# Reaccion-vReg.net
KiCad netlist of a schematic drawn in EAGLE
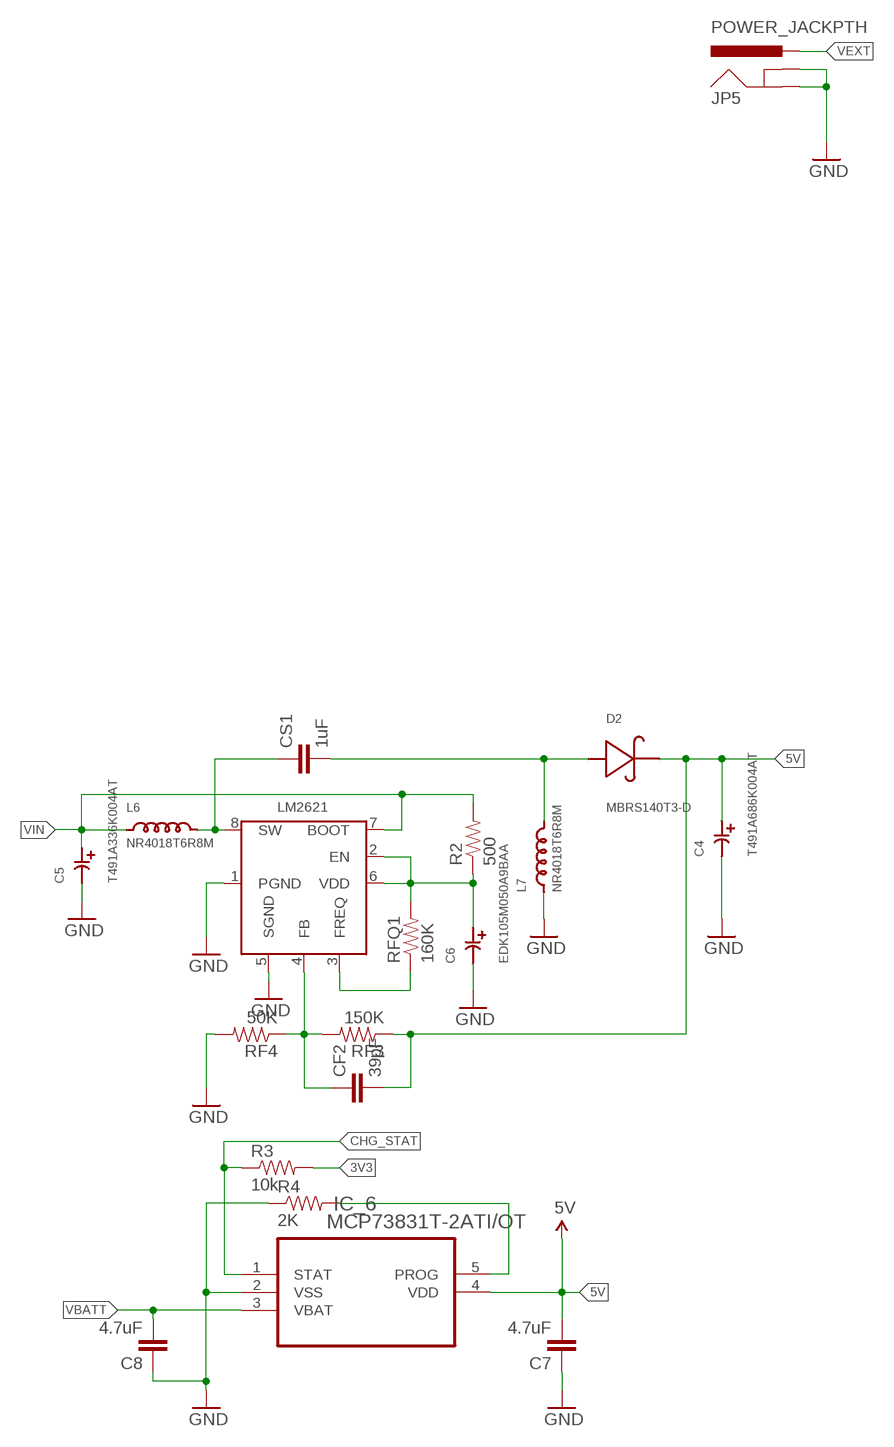
[diagram p0: schematic, sheet 1]

(export (version "E")
  (design (tool "Eeschema 10.0.6"))
  (components
    (comp (ref "C4")
      (value "T491A686K004AT")
      (footprint "eagle-import:3216-18")
      (libsource (lib "eagle-import") (part "T491A686K004AT"))
    )
    (comp (ref "C5")
      (value "T491A336K004AT")
      (footprint "eagle-import:3216-18")
      (libsource (lib "eagle-import") (part "T491A336K004AT"))
    )
    (comp (ref "C6")
      (value "EDK105M050A9BAA")
      (footprint "eagle-import:EDK105M050A9BAA")
      (libsource (lib "eagle-import") (part "EDK105M050A9BAA"))
    )
    (comp (ref "C7")
      (value "4.7uF")
      (footprint "eagle-import:0805")
      (libsource (lib "eagle-import") (part "CAP0805"))
    )
    (comp (ref "C8")
      (value "4.7uF")
      (footprint "eagle-import:0805")
      (libsource (lib "eagle-import") (part "CAP0805"))
    )
    (comp (ref "CF2")
      (value "39pF")
      (footprint "eagle-import:0805")
      (libsource (lib "eagle-import") (part "CAP0805"))
    )
    (comp (ref "CS1")
      (value "1uF")
      (footprint "eagle-import:0805")
      (libsource (lib "eagle-import") (part "CAP0805"))
    )
    (comp (ref "D2")
      (value "MBRS140T3-D")
      (footprint "eagle-import:MBRS140T3G")
      (libsource (lib "eagle-import") (part "MBRS140T3-D"))
    )
    (comp (ref "IC_4")
      (value "LM2621")
      (footprint "eagle-import:R-PDSO-G8")
      (libsource (lib "eagle-import") (part "LM2621"))
    )
    (comp (ref "IC_6")
      (value "MCP73831T-2ATI/OT")
      (footprint "eagle-import:SOT95P300X145-5N")
      (libsource (lib "eagle-import") (part "MCP73831T-2ATI/OT"))
    )
    (comp (ref "JP5")
      (value "POWER_JACKPTH")
      (footprint "eagle-import:POWER_JACK_PTH")
      (libsource (lib "eagle-import") (part "POWER_JACKPTH"))
    )
    (comp (ref "L6")
      (value "NR4018T6R8M")
      (footprint "eagle-import:NR4018_NRS4018")
      (libsource (lib "eagle-import") (part "NR4018T6R8M"))
    )
    (comp (ref "L7")
      (value "NR4018T6R8M")
      (footprint "eagle-import:NR4018_NRS4018")
      (libsource (lib "eagle-import") (part "NR4018T6R8M"))
    )
    (comp (ref "R2")
      (value "500")
      (footprint "eagle-import:0805")
      (libsource (lib "eagle-import") (part "RESISTOR0805-RES"))
    )
    (comp (ref "R3")
      (value "10k")
      (footprint "eagle-import:0805")
      (libsource (lib "eagle-import") (part "RESISTOR0805-RES"))
    )
    (comp (ref "R4")
      (value "2K")
      (footprint "eagle-import:0805")
      (libsource (lib "eagle-import") (part "RESISTOR0805-RES"))
    )
    (comp (ref "RF3")
      (value "150K")
      (footprint "eagle-import:0805")
      (libsource (lib "eagle-import") (part "RESISTOR0805-RES"))
    )
    (comp (ref "RF4")
      (value "50K")
      (footprint "eagle-import:0805")
      (libsource (lib "eagle-import") (part "RESISTOR0805-RES"))
    )
    (comp (ref "RFQ1")
      (value "160K")
      (footprint "eagle-import:0805")
      (libsource (lib "eagle-import") (part "RESISTOR0805-RES"))
    )
  )
  (nets
    (net (code "1") (name "3V3") (class "Default")
      (node (ref "R3") (pin "2") (pinfunction "2_2") (pintype "passive"))
    )
    (net (code "2") (name "5V") (class "Default")
      (node (ref "C4") (pin "1") (pinfunction "P$1_1") (pintype "bidirectional"))
      (node (ref "C7") (pin "2") (pinfunction "2_2") (pintype "passive"))
      (node (ref "CF2") (pin "2") (pinfunction "2_2") (pintype "passive"))
      (node (ref "D2") (pin "2") (pinfunction "2_2") (pintype "bidirectional"))
      (node (ref "IC_6") (pin "4") (pinfunction "VDD_4") (pintype "power_in"))
      (node (ref "RF3") (pin "1") (pinfunction "1_1") (pintype "passive"))
    )
    (net (code "3") (name "CHG_STAT") (class "Default")
      (node (ref "IC_6") (pin "1") (pinfunction "STAT_1") (pintype "input"))
      (node (ref "R3") (pin "1") (pinfunction "1_1") (pintype "passive"))
    )
    (net (code "4") (name "GND") (class "Default")
      (node (ref "C4") (pin "2") (pinfunction "P$2_2") (pintype "bidirectional"))
      (node (ref "C5") (pin "2") (pinfunction "P$2_2") (pintype "bidirectional"))
      (node (ref "C6") (pin "P$2") (pinfunction "P$2_P$2") (pintype "bidirectional"))
      (node (ref "C7") (pin "1") (pinfunction "1_1") (pintype "passive"))
      (node (ref "C8") (pin "1") (pinfunction "1_1") (pintype "passive"))
      (node (ref "IC_4") (pin "1") (pinfunction "PGND_1") (pintype "bidirectional"))
      (node (ref "IC_4") (pin "5") (pinfunction "SGND_5") (pintype "bidirectional"))
      (node (ref "IC_6") (pin "2") (pinfunction "VSS_2") (pintype "passive"))
      (node (ref "JP5") (pin "GND") (pinfunction "GND_GND") (pintype "bidirectional"))
      (node (ref "JP5") (pin "GNDBREAK") (pinfunction "GNDBREAK_GNDBREAK") (pintype "bidirectional"))
      (node (ref "L7") (pin "P$1") (pinfunction "P$1_P$1") (pintype "bidirectional"))
      (node (ref "R4") (pin "1") (pinfunction "1_1") (pintype "passive"))
      (node (ref "RF4") (pin "2") (pinfunction "2_2") (pintype "passive"))
    )
    (net (code "5") (name "Net-(CS1-Pad2)") (class "Default")
      (node (ref "CS1") (pin "2") (pinfunction "2_2") (pintype "passive"))
      (node (ref "D2") (pin "1") (pinfunction "1_1") (pintype "bidirectional"))
      (node (ref "L7") (pin "P$2") (pinfunction "P$2_P$2") (pintype "bidirectional"))
    )
    (net (code "6") (name "Net-(IC_4-EN)") (class "Default")
      (node (ref "C6") (pin "P$1") (pinfunction "P$1_P$1") (pintype "bidirectional"))
      (node (ref "IC_4") (pin "2") (pinfunction "EN_2") (pintype "bidirectional"))
      (node (ref "IC_4") (pin "6") (pinfunction "VDD_6") (pintype "bidirectional"))
      (node (ref "R2") (pin "1") (pinfunction "1_1") (pintype "passive"))
      (node (ref "RFQ1") (pin "2") (pinfunction "2_2") (pintype "passive"))
    )
    (net (code "7") (name "Net-(IC_4-FB)") (class "Default")
      (node (ref "CF2") (pin "1") (pinfunction "1_1") (pintype "passive"))
      (node (ref "IC_4") (pin "4") (pinfunction "FB_4") (pintype "bidirectional"))
      (node (ref "RF3") (pin "2") (pinfunction "2_2") (pintype "passive"))
      (node (ref "RF4") (pin "1") (pinfunction "1_1") (pintype "passive"))
    )
    (net (code "8") (name "Net-(IC_4-FREQ)") (class "Default")
      (node (ref "IC_4") (pin "3") (pinfunction "FREQ_3") (pintype "bidirectional"))
      (node (ref "RFQ1") (pin "1") (pinfunction "1_1") (pintype "passive"))
    )
    (net (code "9") (name "Net-(IC_4-SW)") (class "Default")
      (node (ref "CS1") (pin "1") (pinfunction "1_1") (pintype "passive"))
      (node (ref "IC_4") (pin "8") (pinfunction "SW_8") (pintype "bidirectional"))
      (node (ref "L6") (pin "P$2") (pinfunction "P$2_P$2") (pintype "bidirectional"))
    )
    (net (code "10") (name "Net-(IC_6-PROG)") (class "Default")
      (node (ref "IC_6") (pin "5") (pinfunction "PROG_5") (pintype "input"))
      (node (ref "R4") (pin "2") (pinfunction "2_2") (pintype "passive"))
    )
    (net (code "11") (name "VBATT") (class "Default")
      (node (ref "C8") (pin "2") (pinfunction "2_2") (pintype "passive"))
      (node (ref "IC_6") (pin "3") (pinfunction "VBAT_3") (pintype "input"))
    )
    (net (code "12") (name "VEXT") (class "Default")
      (node (ref "JP5") (pin "PWR") (pinfunction "PWR_PWR") (pintype "bidirectional"))
    )
    (net (code "13") (name "VIN") (class "Default")
      (node (ref "C5") (pin "1") (pinfunction "P$1_1") (pintype "bidirectional"))
      (node (ref "IC_4") (pin "7") (pinfunction "BOOT_7") (pintype "bidirectional"))
      (node (ref "L6") (pin "P$1") (pinfunction "P$1_P$1") (pintype "bidirectional"))
      (node (ref "R2") (pin "2") (pinfunction "2_2") (pintype "passive"))
    )
  )
)
